# BARRERA.net
KiCad netlist of a schematic drawn in EAGLE
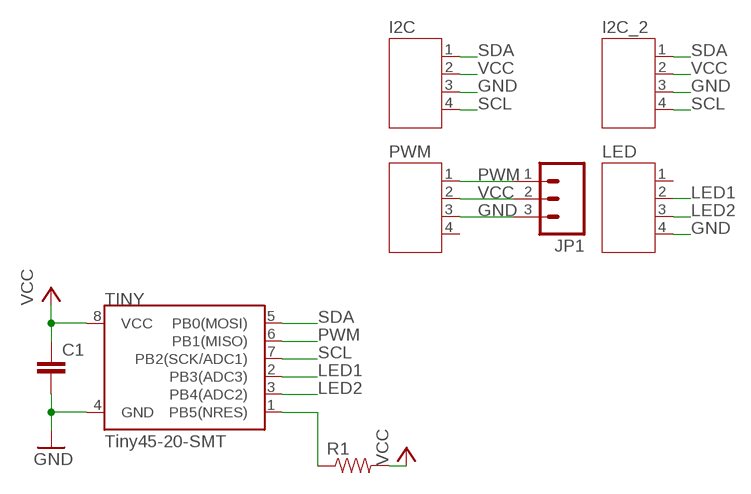
[diagram p0: schematic, sheet 1]

(export (version "E")
  (design (tool "Eeschema 10.0.6"))
  (components
    (comp (ref "C1")
      (value "CAP0603-CAP")
      (footprint "eagle-import:0603-CAP")
      (libsource (lib "eagle-import") (part "CAP0603-CAP"))
    )
    (comp (ref "I2C")
      (value "JST-PH4")
      (footprint "eagle-import:JST-PH4")
      (libsource (lib "eagle-import") (part "JST-PH4"))
    )
    (comp (ref "I2C_2")
      (value "JST-PH4")
      (footprint "eagle-import:JST-PH4")
      (libsource (lib "eagle-import") (part "JST-PH4"))
    )
    (comp (ref "JP1")
      (value "M03PTH")
      (footprint "eagle-import:1X03")
      (libsource (lib "eagle-import") (part "M03PTH"))
    )
    (comp (ref "LED")
      (value "JST-PH4")
      (footprint "eagle-import:JST-PH4")
      (libsource (lib "eagle-import") (part "JST-PH4"))
    )
    (comp (ref "PWM")
      (value "JST-PH4")
      (footprint "eagle-import:JST-PH4")
      (libsource (lib "eagle-import") (part "JST-PH4"))
    )
    (comp (ref "R1")
      (value "RESISTOR0603")
      (footprint "eagle-import:0603-RES")
      (libsource (lib "eagle-import") (part "RESISTOR0603"))
    )
    (comp (ref "TINY")
      (value "Tiny45-20-SMT")
      (footprint "eagle-import:SO08-EIAJ")
      (libsource (lib "eagle-import") (part "ATTINY45TINY45-20-SMT"))
    )
  )
  (nets
    (net (code "1") (name "/LED1") (class "Default")
      (node (ref "LED") (pin "2") (pinfunction "2_2") (pintype "passive"))
      (node (ref "TINY") (pin "2") (pinfunction "PB3(ADC3)_2") (pintype "bidirectional"))
    )
    (net (code "2") (name "/LED2") (class "Default")
      (node (ref "LED") (pin "3") (pinfunction "3_3") (pintype "passive"))
      (node (ref "TINY") (pin "3") (pinfunction "PB4(ADC2)_3") (pintype "bidirectional"))
    )
    (net (code "3") (name "/PWM") (class "Default")
      (node (ref "JP1") (pin "1") (pinfunction "1_1") (pintype "passive"))
      (node (ref "PWM") (pin "1") (pinfunction "1_1") (pintype "passive"))
      (node (ref "TINY") (pin "6") (pinfunction "PB1(MISO)_6") (pintype "bidirectional"))
    )
    (net (code "4") (name "/SCL") (class "Default")
      (node (ref "I2C") (pin "4") (pinfunction "4_4") (pintype "passive"))
      (node (ref "I2C_2") (pin "4") (pinfunction "4_4") (pintype "passive"))
      (node (ref "TINY") (pin "7") (pinfunction "PB2(SCK/ADC1)_7") (pintype "bidirectional"))
    )
    (net (code "5") (name "/SDA") (class "Default")
      (node (ref "I2C") (pin "1") (pinfunction "1_1") (pintype "passive"))
      (node (ref "I2C_2") (pin "1") (pinfunction "1_1") (pintype "passive"))
      (node (ref "TINY") (pin "5") (pinfunction "PB0(MOSI)_5") (pintype "bidirectional"))
    )
    (net (code "6") (name "GND") (class "Default")
      (node (ref "C1") (pin "2") (pinfunction "2_2") (pintype "passive"))
      (node (ref "I2C") (pin "3") (pinfunction "3_3") (pintype "passive"))
      (node (ref "I2C_2") (pin "3") (pinfunction "3_3") (pintype "passive"))
      (node (ref "JP1") (pin "3") (pinfunction "3_3") (pintype "passive"))
      (node (ref "LED") (pin "4") (pinfunction "4_4") (pintype "passive"))
      (node (ref "PWM") (pin "3") (pinfunction "3_3") (pintype "passive"))
      (node (ref "TINY") (pin "4") (pinfunction "GND_4") (pintype "bidirectional"))
    )
    (net (code "7") (name "Net-(TINY-PB5(NRES))") (class "Default")
      (node (ref "R1") (pin "1") (pinfunction "1_1") (pintype "passive"))
      (node (ref "TINY") (pin "1") (pinfunction "PB5(NRES)_1") (pintype "bidirectional"))
    )
    (net (code "8") (name "VCC") (class "Default")
      (node (ref "C1") (pin "1") (pinfunction "1_1") (pintype "passive"))
      (node (ref "I2C") (pin "2") (pinfunction "2_2") (pintype "passive"))
      (node (ref "I2C_2") (pin "2") (pinfunction "2_2") (pintype "passive"))
      (node (ref "JP1") (pin "2") (pinfunction "2_2") (pintype "passive"))
      (node (ref "PWM") (pin "2") (pinfunction "2_2") (pintype "passive"))
      (node (ref "R1") (pin "2") (pinfunction "2_2") (pintype "passive"))
      (node (ref "TINY") (pin "8") (pinfunction "VCC_8") (pintype "bidirectional"))
    )
    (net (code "9") (name "unconnected-(LED-Pad1)") (class "Default")
      (node (ref "LED") (pin "1") (pinfunction "1_1") (pintype "passive"))
    )
    (net (code "10") (name "unconnected-(PWM-Pad4)") (class "Default")
      (node (ref "PWM") (pin "4") (pinfunction "4_4") (pintype "passive"))
    )
  )
)
